# 04-Sensors.net
KiCad netlist of a schematic drawn in Altium Designer
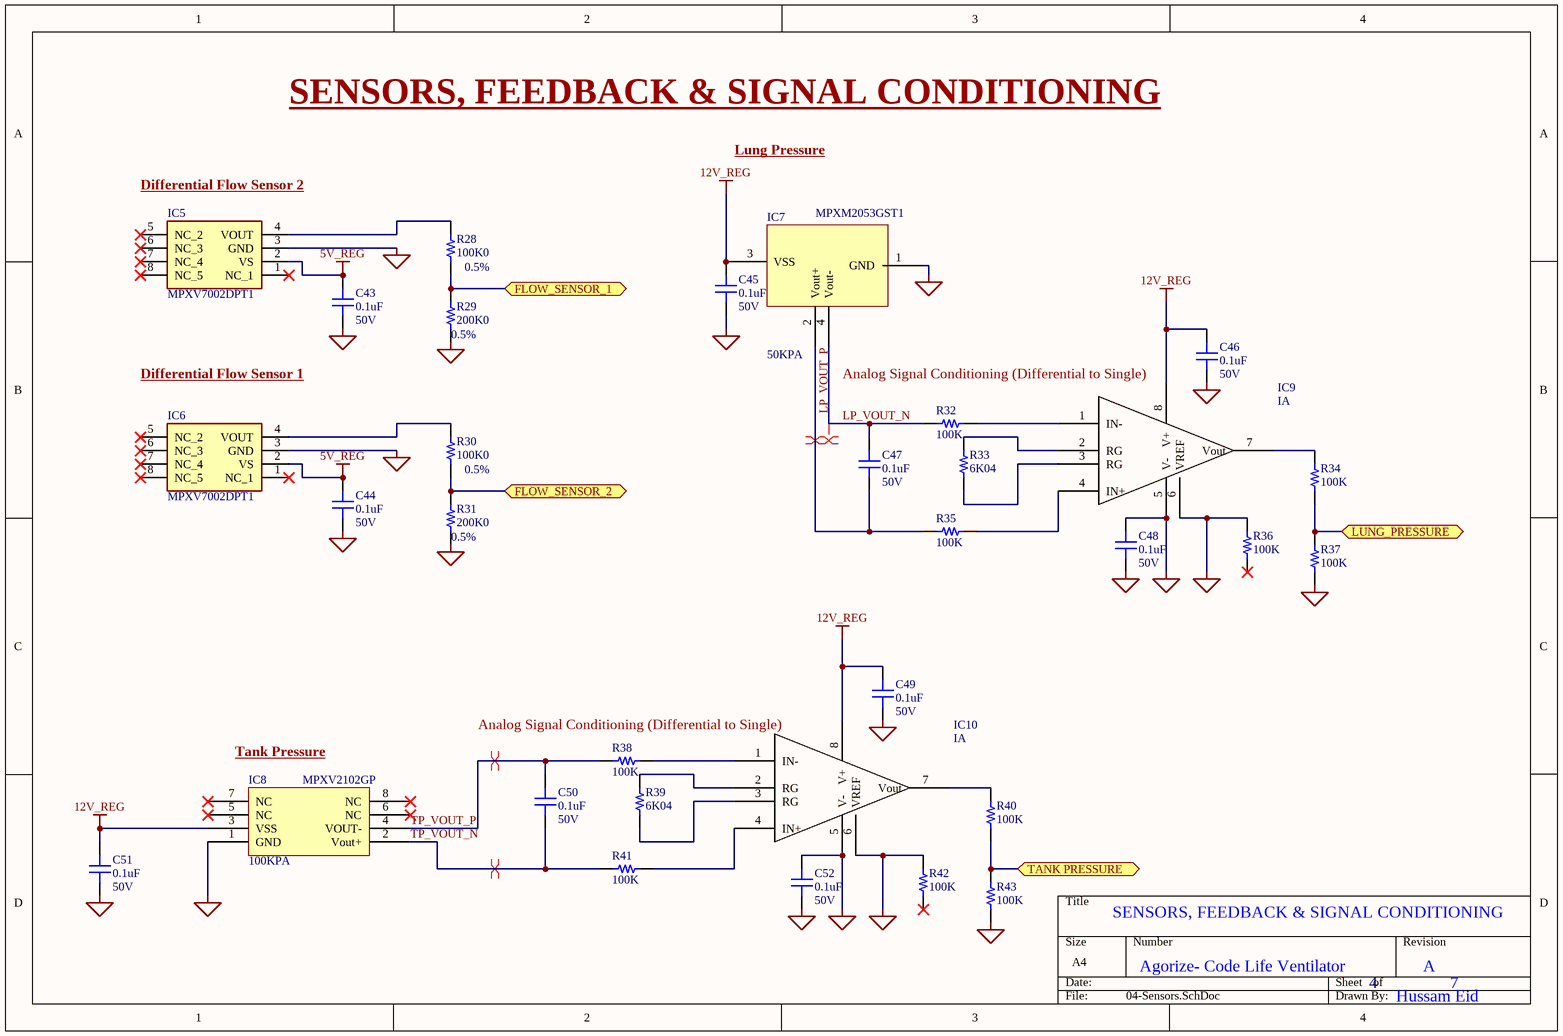
[diagram p0: 04-Sensors.SchDoc]

(export (version "E")
  (design (tool "Eeschema 10.0.6"))
  (components
    (comp (ref "C43")
      (value "0.1uF")
      (footprint "CAP 0603/1608")
      (description "CAP CER 0.1UF 50V X7R 0603")
      (fields (field (name "TOLERANCE") "20%") (field (name "VOLTAGE RATING") "50V"))
      (libsource (lib "Celestial Library Database") (part "Capacitor"))
    )
    (comp (ref "C44")
      (value "0.1uF")
      (footprint "CAP 0603/1608")
      (description "CAP CER 0.1UF 50V X7R 0603")
      (fields (field (name "TOLERANCE") "20%") (field (name "VOLTAGE RATING") "50V"))
      (libsource (lib "Celestial Library Database") (part "Capacitor"))
    )
    (comp (ref "C45")
      (value "0.1uF")
      (footprint "CAP 0603/1608")
      (description "CAP CER 0.1UF 50V X7R 0603")
      (fields (field (name "TOLERANCE") "20%") (field (name "VOLTAGE RATING") "50V"))
      (libsource (lib "Celestial Library Database") (part "Capacitor"))
    )
    (comp (ref "C46")
      (value "0.1uF")
      (footprint "CAP 0603/1608")
      (description "CAP CER 0.1UF 50V X7R 0603")
      (fields (field (name "TOLERANCE") "20%") (field (name "VOLTAGE RATING") "50V"))
      (libsource (lib "Celestial Library Database") (part "Capacitor"))
    )
    (comp (ref "C47")
      (value "0.1uF")
      (footprint "CAP 0603/1608")
      (description "CAP CER 0.1UF 50V X7R 0603")
      (fields (field (name "TOLERANCE") "20%") (field (name "VOLTAGE RATING") "50V"))
      (libsource (lib "Celestial Library Database") (part "Capacitor"))
    )
    (comp (ref "C48")
      (value "0.1uF")
      (footprint "CAP 0603/1608")
      (description "CAP CER 0.1UF 50V X7R 0603")
      (fields (field (name "TOLERANCE") "20%") (field (name "VOLTAGE RATING") "50V"))
      (libsource (lib "Celestial Library Database") (part "Capacitor"))
    )
    (comp (ref "C49")
      (value "0.1uF")
      (footprint "CAP 0603/1608")
      (description "CAP CER 0.1UF 50V X7R 0603")
      (fields (field (name "TOLERANCE") "20%") (field (name "VOLTAGE RATING") "50V"))
      (libsource (lib "Celestial Library Database") (part "Capacitor"))
    )
    (comp (ref "C50")
      (value "0.1uF")
      (footprint "CAP 0603/1608")
      (description "CAP CER 0.1UF 50V X7R 0603")
      (fields (field (name "TOLERANCE") "20%") (field (name "VOLTAGE RATING") "50V"))
      (libsource (lib "Celestial Library Database") (part "Capacitor"))
    )
    (comp (ref "C51")
      (value "0.1uF")
      (footprint "CAP 0603/1608")
      (description "CAP CER 0.1UF 50V X7R 0603")
      (fields (field (name "TOLERANCE") "20%") (field (name "VOLTAGE RATING") "50V"))
      (libsource (lib "Celestial Library Database") (part "Capacitor"))
    )
    (comp (ref "C52")
      (value "0.1uF")
      (footprint "CAP 0603/1608")
      (description "CAP CER 0.1UF 50V X7R 0603")
      (fields (field (name "TOLERANCE") "20%") (field (name "VOLTAGE RATING") "50V"))
      (libsource (lib "Celestial Library Database") (part "Capacitor"))
    )
    (comp (ref "IC5")
      (value "MPXV7002DPT1")
      (footprint "SamacSys:MPXV7002DPT1")
      (description "PRESSURE SENSOR DUAL PORT 8SOP")
      (fields (field (name "MOUSER PART NUMBER") "841-MPXV7002DPT1"))
      (libsource (lib "*") (part "MPXV7002DPT1"))
    )
    (comp (ref "IC6")
      (value "MPXV7002DPT1")
      (footprint "SamacSys:MPXV7002DPT1")
      (description "PRESSURE SENSOR DUAL PORT 8SOP")
      (fields (field (name "MOUSER PART NUMBER") "841-MPXV7002DPT1"))
      (libsource (lib "*") (part "MPXV7002DPT1"))
    )
    (comp (ref "IC7")
      (value "50KPA")
      (footprint "DPAK127P1219X1008-5N")
      (description "SENS PRESSURE 7.25 PSI MAX MPAK")
      (fields (field (name "MANUFACTURER PART NUMBER 1") "MPXM2053GST1"))
      (libsource (lib "Schlib1") (part "Pressure Sensor"))
    )
    (comp (ref "IC8")
      (value "100KPA")
      (footprint "SOP127P600-8N")
      (description "SENSOR GAUGE PRESS 14.5PSI MAX")
      (fields (field (name "MANUFACTURER PART NUMBER 1") "MPXV2102GP"))
      (libsource (lib "Schlib1") (part "100KPA Pressure Sensor"))
    )
    (comp (ref "IC9")
      (value "IA")
      (footprint "SOP65P490X110-8N")
      (description "IC INST AMP 1 CIRCUIT 8VSSOP")
      (libsource (lib "Schlib1") (part "IA"))
    )
    (comp (ref "IC10")
      (value "IA")
      (footprint "SOP65P490X110-8N")
      (description "IC INST AMP 1 CIRCUIT 8VSSOP")
      (libsource (lib "Schlib1") (part "IA"))
    )
    (comp (ref "R28")
      (value "100K0")
      (footprint "RES 0603/1608")
      (description "RES SMD 100K OHM 0.5% 1/16W 0603")
      (fields (field (name "TOLERANCE") "0.5%"))
      (libsource (lib "Celestial Library Database") (part "Resistor"))
    )
    (comp (ref "R29")
      (value "200K0")
      (footprint "RES 0603/1608")
      (description "RES SMD 200K OHM 0.5% 1/16W 0603")
      (fields (field (name "TOLERANCE") "0.5%"))
      (libsource (lib "Celestial Library Database") (part "Resistor"))
    )
    (comp (ref "R30")
      (value "100K0")
      (footprint "RES 0603/1608")
      (description "RES SMD 100K OHM 0.5% 1/16W 0603")
      (fields (field (name "TOLERANCE") "0.5%"))
      (libsource (lib "Celestial Library Database") (part "Resistor"))
    )
    (comp (ref "R31")
      (value "200K0")
      (footprint "RES 0603/1608")
      (description "RES SMD 200K OHM 0.5% 1/16W 0603")
      (fields (field (name "TOLERANCE") "0.5%"))
      (libsource (lib "Celestial Library Database") (part "Resistor"))
    )
    (comp (ref "R32")
      (value "100K")
      (footprint "RES 0603/1608")
      (description "RES SMD100K OHM 0.5% 1/16W 0603")
      (fields (field (name "TOLERANCE") "0.5%"))
      (libsource (lib "Celestial Library Database") (part "Resistor"))
    )
    (comp (ref "R33")
      (value "6K04")
      (footprint "RES 0603/1608")
      (description "RES SMD 6K04 OHM 0.5% 1/16W 0603")
      (fields (field (name "TOLERANCE") "1%"))
      (libsource (lib "Celestial Library Database") (part "Resistor"))
    )
    (comp (ref "R34")
      (value "100K")
      (footprint "RES 0603/1608")
      (description "RES SMD100K OHM 0.5% 1/16W 0603")
      (fields (field (name "TOLERANCE") "0.5%"))
      (libsource (lib "Celestial Library Database") (part "Resistor"))
    )
    (comp (ref "R35")
      (value "100K")
      (footprint "RES 0603/1608")
      (description "RES SMD100K OHM 0.5% 1/16W 0603")
      (fields (field (name "TOLERANCE") "0.5%"))
      (libsource (lib "Celestial Library Database") (part "Resistor"))
    )
    (comp (ref "R36")
      (value "100K")
      (footprint "RES 0603/1608")
      (description "RES SMD100K OHM 0.5% 1/16W 0603")
      (fields (field (name "TOLERANCE") "0.5%"))
      (libsource (lib "Celestial Library Database") (part "Resistor"))
    )
    (comp (ref "R37")
      (value "100K")
      (footprint "RES 0603/1608")
      (description "RES SMD100K OHM 0.5% 1/16W 0603")
      (fields (field (name "TOLERANCE") "0.5%"))
      (libsource (lib "Celestial Library Database") (part "Resistor"))
    )
    (comp (ref "R38")
      (value "100K")
      (footprint "RES 0603/1608")
      (description "RES SMD100K OHM 0.5% 1/16W 0603")
      (fields (field (name "TOLERANCE") "0.5%"))
      (libsource (lib "Celestial Library Database") (part "Resistor"))
    )
    (comp (ref "R39")
      (value "6K04")
      (footprint "RES 0603/1608")
      (description "RES SMD 6K04 OHM 0.5% 1/16W 0603")
      (fields (field (name "TOLERANCE") "1%"))
      (libsource (lib "Celestial Library Database") (part "Resistor"))
    )
    (comp (ref "R40")
      (value "100K")
      (footprint "RES 0603/1608")
      (description "RES SMD100K OHM 0.5% 1/16W 0603")
      (fields (field (name "TOLERANCE") "0.5%"))
      (libsource (lib "Celestial Library Database") (part "Resistor"))
    )
    (comp (ref "R41")
      (value "100K")
      (footprint "RES 0603/1608")
      (description "RES SMD100K OHM 0.5% 1/16W 0603")
      (fields (field (name "TOLERANCE") "0.5%"))
      (libsource (lib "Celestial Library Database") (part "Resistor"))
    )
    (comp (ref "R42")
      (value "100K")
      (footprint "RES 0603/1608")
      (description "RES SMD100K OHM 0.5% 1/16W 0603")
      (fields (field (name "TOLERANCE") "0.5%"))
      (libsource (lib "Celestial Library Database") (part "Resistor"))
    )
    (comp (ref "R43")
      (value "100K")
      (footprint "RES 0603/1608")
      (description "RES SMD100K OHM 0.5% 1/16W 0603")
      (fields (field (name "TOLERANCE") "0.5%"))
      (libsource (lib "Celestial Library Database") (part "Resistor"))
    )
  )
  (nets
    (net (code "1") (name "/FLOW_SENSOR_1") (class "Default")
      (node (ref "R28") (pin "1") (pinfunction "1_1") (pintype "passive"))
      (node (ref "R29") (pin "2") (pinfunction "2_2") (pintype "passive"))
    )
    (net (code "2") (name "/FLOW_SENSOR_2") (class "Default")
      (node (ref "R30") (pin "1") (pinfunction "1_1") (pintype "passive"))
      (node (ref "R31") (pin "2") (pinfunction "2_2") (pintype "passive"))
    )
    (net (code "3") (name "/LP_VOUT_N") (class "Default")
      (node (ref "C47") (pin "2") (pinfunction "2_2") (pintype "passive"))
      (node (ref "IC7") (pin "4") (pinfunction "Vout-_4") (pintype "passive"))
      (node (ref "R32") (pin "2") (pinfunction "2_2") (pintype "passive"))
    )
    (net (code "4") (name "/LP_VOUT_P") (class "Default")
      (node (ref "C47") (pin "1") (pinfunction "1_1") (pintype "passive"))
      (node (ref "IC7") (pin "2") (pinfunction "Vout+_2") (pintype "passive"))
      (node (ref "R35") (pin "2") (pinfunction "2_2") (pintype "passive"))
    )
    (net (code "5") (name "/LUNG_PRESSURE") (class "Default")
      (node (ref "R34") (pin "2") (pinfunction "2_2") (pintype "passive"))
      (node (ref "R37") (pin "1") (pinfunction "1_1") (pintype "passive"))
    )
    (net (code "6") (name "/TANK PRESSURE") (class "Default")
      (node (ref "R40") (pin "2") (pinfunction "2_2") (pintype "passive"))
      (node (ref "R43") (pin "1") (pinfunction "1_1") (pintype "passive"))
    )
    (net (code "7") (name "/TP_VOUT_N") (class "Default")
      (node (ref "C50") (pin "1") (pinfunction "1_1") (pintype "passive"))
      (node (ref "IC8") (pin "2") (pinfunction "Vout+_2") (pintype "passive"))
      (node (ref "R41") (pin "2") (pinfunction "2_2") (pintype "passive"))
    )
    (net (code "8") (name "/TP_VOUT_P") (class "Default")
      (node (ref "C50") (pin "2") (pinfunction "2_2") (pintype "passive"))
      (node (ref "IC8") (pin "4") (pinfunction "VOUT-_4") (pintype "passive"))
      (node (ref "R38") (pin "2") (pinfunction "2_2") (pintype "passive"))
    )
    (net (code "9") (name "5V_REG") (class "Default")
      (node (ref "C43") (pin "1") (pinfunction "1_1") (pintype "passive"))
      (node (ref "C44") (pin "1") (pinfunction "1_1") (pintype "passive"))
      (node (ref "IC5") (pin "2") (pinfunction "VS_2") (pintype "passive"))
      (node (ref "IC6") (pin "2") (pinfunction "VS_2") (pintype "passive"))
    )
    (net (code "10") (name "12V_REG") (class "Default")
      (node (ref "C45") (pin "1") (pinfunction "1_1") (pintype "passive"))
      (node (ref "C46") (pin "2") (pinfunction "2_2") (pintype "passive"))
      (node (ref "C49") (pin "2") (pinfunction "2_2") (pintype "passive"))
      (node (ref "C51") (pin "2") (pinfunction "2_2") (pintype "passive"))
      (node (ref "IC10") (pin "8") (pinfunction "V+_8") (pintype "passive"))
      (node (ref "IC7") (pin "3") (pinfunction "VSS_3") (pintype "passive"))
      (node (ref "IC8") (pin "3") (pinfunction "VSS_3") (pintype "passive"))
      (node (ref "IC9") (pin "8") (pinfunction "V+_8") (pintype "passive"))
    )
    (net (code "11") (name "COM") (class "Default")
      (node (ref "C43") (pin "2") (pinfunction "2_2") (pintype "passive"))
      (node (ref "C44") (pin "2") (pinfunction "2_2") (pintype "passive"))
      (node (ref "C45") (pin "2") (pinfunction "2_2") (pintype "passive"))
      (node (ref "C46") (pin "1") (pinfunction "1_1") (pintype "passive"))
      (node (ref "C48") (pin "1") (pinfunction "1_1") (pintype "passive"))
      (node (ref "C48") (pin "2") (pinfunction "2_2") (pintype "passive"))
      (node (ref "C49") (pin "1") (pinfunction "1_1") (pintype "passive"))
      (node (ref "C51") (pin "1") (pinfunction "1_1") (pintype "passive"))
      (node (ref "C52") (pin "1") (pinfunction "1_1") (pintype "passive"))
      (node (ref "C52") (pin "2") (pinfunction "2_2") (pintype "passive"))
      (node (ref "IC10") (pin "5") (pinfunction "V-_5") (pintype "passive"))
      (node (ref "IC10") (pin "6") (pinfunction "VREF_6") (pintype "passive"))
      (node (ref "IC5") (pin "3") (pinfunction "GND_3") (pintype "passive"))
      (node (ref "IC6") (pin "3") (pinfunction "GND_3") (pintype "passive"))
      (node (ref "IC7") (pin "1") (pinfunction "GND_1") (pintype "passive"))
      (node (ref "IC8") (pin "1") (pinfunction "GND_1") (pintype "passive"))
      (node (ref "IC9") (pin "5") (pinfunction "V-_5") (pintype "passive"))
      (node (ref "IC9") (pin "6") (pinfunction "VREF_6") (pintype "passive"))
      (node (ref "R29") (pin "1") (pinfunction "1_1") (pintype "passive"))
      (node (ref "R31") (pin "1") (pinfunction "1_1") (pintype "passive"))
      (node (ref "R36") (pin "1") (pinfunction "1_1") (pintype "passive"))
      (node (ref "R37") (pin "2") (pinfunction "2_2") (pintype "passive"))
      (node (ref "R42") (pin "1") (pinfunction "1_1") (pintype "passive"))
      (node (ref "R43") (pin "2") (pinfunction "2_2") (pintype "passive"))
    )
    (net (code "12") (name "Net-(IC5-VOUT)") (class "Default")
      (node (ref "IC5") (pin "4") (pinfunction "VOUT_4") (pintype "passive"))
      (node (ref "R28") (pin "2") (pinfunction "2_2") (pintype "passive"))
    )
    (net (code "13") (name "Net-(IC6-VOUT)") (class "Default")
      (node (ref "IC6") (pin "4") (pinfunction "VOUT_4") (pintype "passive"))
      (node (ref "R30") (pin "2") (pinfunction "2_2") (pintype "passive"))
    )
    (net (code "14") (name "Net-(IC9-IN+)") (class "Default")
      (node (ref "IC9") (pin "4") (pinfunction "IN+_4") (pintype "passive"))
      (node (ref "R35") (pin "1") (pinfunction "1_1") (pintype "passive"))
    )
    (net (code "15") (name "Net-(IC9-IN-)") (class "Default")
      (node (ref "IC9") (pin "1") (pinfunction "IN-_1") (pintype "passive"))
      (node (ref "R32") (pin "1") (pinfunction "1_1") (pintype "passive"))
    )
    (net (code "16") (name "Net-(IC9-RG-Pad2)") (class "Default")
      (node (ref "IC9") (pin "2") (pinfunction "RG_2") (pintype "passive"))
      (node (ref "R33") (pin "2") (pinfunction "2_2") (pintype "passive"))
    )
    (net (code "17") (name "Net-(IC9-RG-Pad3)") (class "Default")
      (node (ref "IC9") (pin "3") (pinfunction "RG_3") (pintype "passive"))
      (node (ref "R33") (pin "1") (pinfunction "1_1") (pintype "passive"))
    )
    (net (code "18") (name "Net-(IC9-Vout)") (class "Default")
      (node (ref "IC9") (pin "7") (pinfunction "Vout_7") (pintype "passive"))
      (node (ref "R34") (pin "1") (pinfunction "1_1") (pintype "passive"))
    )
    (net (code "19") (name "Net-(IC10-IN+)") (class "Default")
      (node (ref "IC10") (pin "4") (pinfunction "IN+_4") (pintype "passive"))
      (node (ref "R41") (pin "1") (pinfunction "1_1") (pintype "passive"))
    )
    (net (code "20") (name "Net-(IC10-IN-)") (class "Default")
      (node (ref "IC10") (pin "1") (pinfunction "IN-_1") (pintype "passive"))
      (node (ref "R38") (pin "1") (pinfunction "1_1") (pintype "passive"))
    )
    (net (code "21") (name "Net-(IC10-RG-Pad2)") (class "Default")
      (node (ref "IC10") (pin "2") (pinfunction "RG_2") (pintype "passive"))
      (node (ref "R39") (pin "2") (pinfunction "2_2") (pintype "passive"))
    )
    (net (code "22") (name "Net-(IC10-RG-Pad3)") (class "Default")
      (node (ref "IC10") (pin "3") (pinfunction "RG_3") (pintype "passive"))
      (node (ref "R39") (pin "1") (pinfunction "1_1") (pintype "passive"))
    )
    (net (code "23") (name "Net-(IC10-Vout)") (class "Default")
      (node (ref "IC10") (pin "7") (pinfunction "Vout_7") (pintype "passive"))
      (node (ref "R40") (pin "1") (pinfunction "1_1") (pintype "passive"))
    )
    (net (code "24") (name "unconnected-(IC5-NC_1-Pad1)") (class "Default")
      (node (ref "IC5") (pin "1") (pinfunction "NC_1_1") (pintype "passive+no_connect"))
    )
    (net (code "25") (name "unconnected-(IC5-NC_2-Pad5)") (class "Default")
      (node (ref "IC5") (pin "5") (pinfunction "NC_2_5") (pintype "passive+no_connect"))
    )
    (net (code "26") (name "unconnected-(IC5-NC_3-Pad6)") (class "Default")
      (node (ref "IC5") (pin "6") (pinfunction "NC_3_6") (pintype "passive+no_connect"))
    )
    (net (code "27") (name "unconnected-(IC5-NC_4-Pad7)") (class "Default")
      (node (ref "IC5") (pin "7") (pinfunction "NC_4_7") (pintype "passive+no_connect"))
    )
    (net (code "28") (name "unconnected-(IC5-NC_5-Pad8)") (class "Default")
      (node (ref "IC5") (pin "8") (pinfunction "NC_5_8") (pintype "passive+no_connect"))
    )
    (net (code "29") (name "unconnected-(IC6-NC_1-Pad1)") (class "Default")
      (node (ref "IC6") (pin "1") (pinfunction "NC_1_1") (pintype "passive+no_connect"))
    )
    (net (code "30") (name "unconnected-(IC6-NC_2-Pad5)") (class "Default")
      (node (ref "IC6") (pin "5") (pinfunction "NC_2_5") (pintype "passive+no_connect"))
    )
    (net (code "31") (name "unconnected-(IC6-NC_3-Pad6)") (class "Default")
      (node (ref "IC6") (pin "6") (pinfunction "NC_3_6") (pintype "passive+no_connect"))
    )
    (net (code "32") (name "unconnected-(IC6-NC_4-Pad7)") (class "Default")
      (node (ref "IC6") (pin "7") (pinfunction "NC_4_7") (pintype "passive+no_connect"))
    )
    (net (code "33") (name "unconnected-(IC6-NC_5-Pad8)") (class "Default")
      (node (ref "IC6") (pin "8") (pinfunction "NC_5_8") (pintype "passive+no_connect"))
    )
    (net (code "34") (name "unconnected-(IC8-NC-Pad5)") (class "Default")
      (node (ref "IC8") (pin "5") (pinfunction "NC_5") (pintype "passive+no_connect"))
    )
    (net (code "35") (name "unconnected-(IC8-NC-Pad6)") (class "Default")
      (node (ref "IC8") (pin "6") (pinfunction "NC_6") (pintype "passive+no_connect"))
    )
    (net (code "36") (name "unconnected-(IC8-NC-Pad7)") (class "Default")
      (node (ref "IC8") (pin "7") (pinfunction "NC_7") (pintype "passive+no_connect"))
    )
    (net (code "37") (name "unconnected-(IC8-NC-Pad8)") (class "Default")
      (node (ref "IC8") (pin "8") (pinfunction "NC_8") (pintype "passive+no_connect"))
    )
    (net (code "38") (name "unconnected-(R36-Pad2)") (class "Default")
      (node (ref "R36") (pin "2") (pinfunction "2_2") (pintype "passive+no_connect"))
    )
    (net (code "39") (name "unconnected-(R42-Pad2)") (class "Default")
      (node (ref "R42") (pin "2") (pinfunction "2_2") (pintype "passive+no_connect"))
    )
  )
)
